# Sheet1.net
KiCad netlist of a schematic drawn in Altium Designer
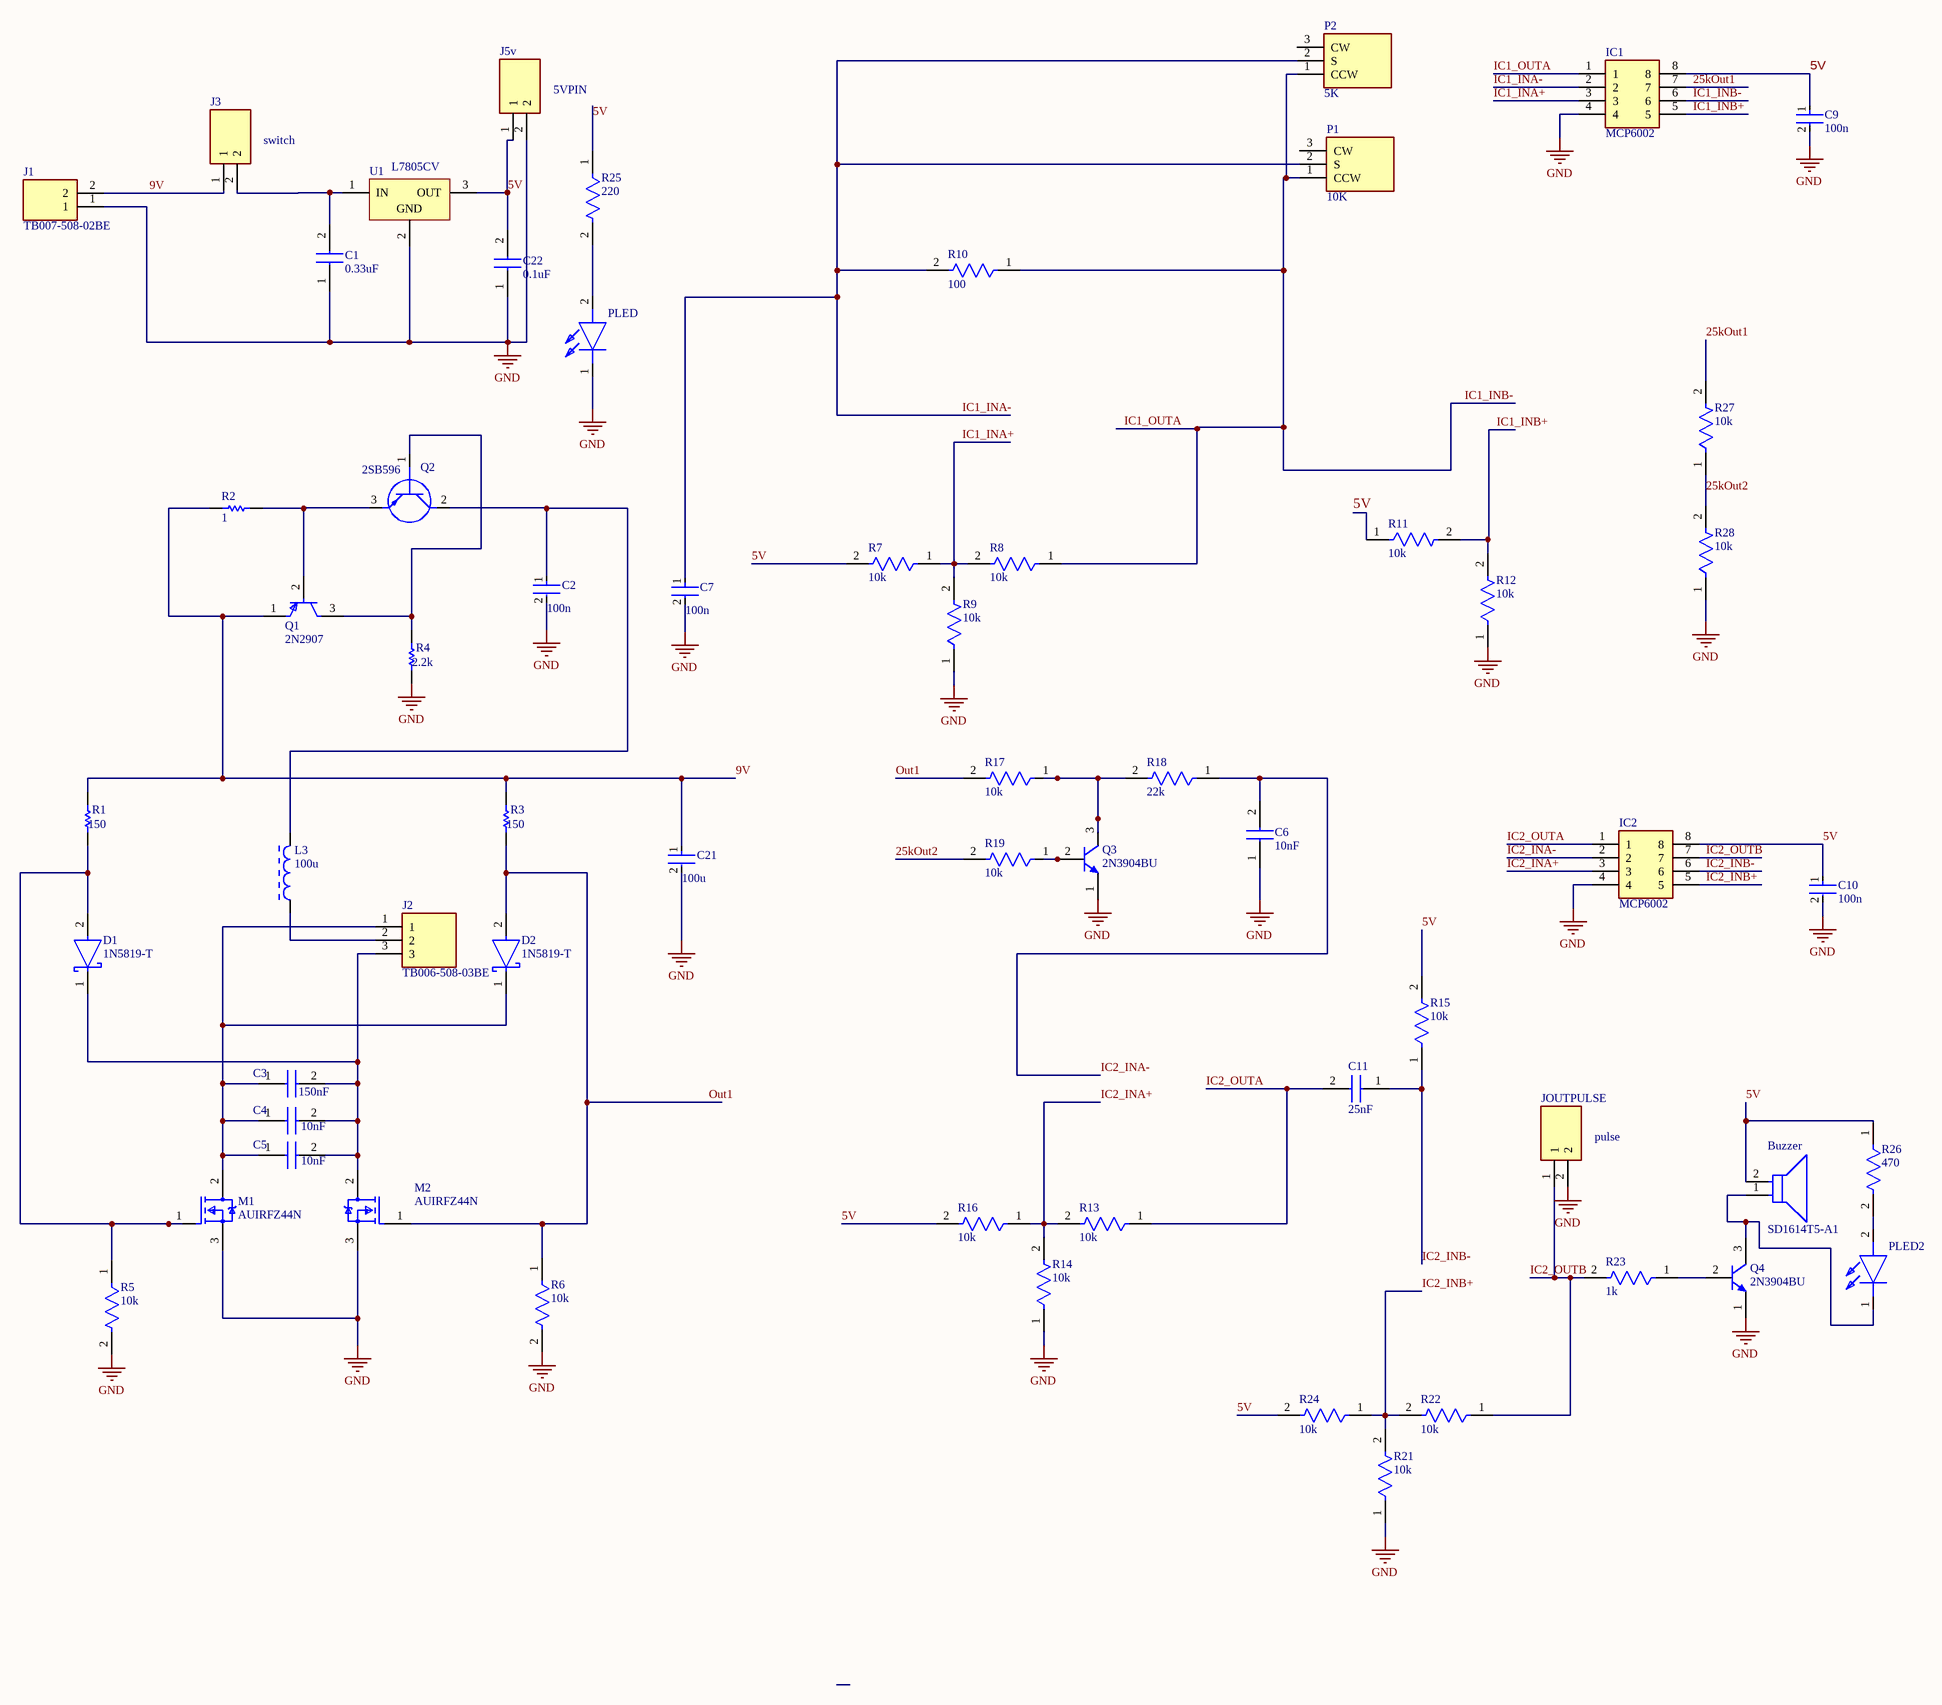
[diagram p0: Sheet1.SchDoc]

(export (version "E")
  (design (tool "Eeschema 10.0.6"))
  (components
    (comp (ref "Buzzer")
      (value "SD1614T5-A1")
      (footprint "FP-SD1614T5-A1-MFG")
      (description "BUZZER MAGNETIC 5V 80DB 2048HZ 1")
      (libsource (lib "Altium Content Vault") (part "e749a21513d54f03b70f810f265f423"))
    )
    (comp (ref "C1")
      (value "0.33uF")
      (footprint "SamacSys:C320C334M5U5TA7301")
      (description "Capacitor")
      (fields
        (field (name "MANUFACTURER_PART_NUMBER") "C320C334M5U5TA7301")
        (field (name "MOUSER PART NUMBER") "80-C320C334M5U5TATU")
      )
      (libsource (lib "*") (part "C320C334M5U5TA7301"))
    )
    (comp (ref "C2")
      (value "100n")
      (footprint "FP-RCE1K1-2_5-MFG")
      (description "Cap Ceramic Monolithic 100nF 100V 10% Thru-Hole Bulk")
      (fields (field (name "TOLERANCE") "10%"))
      (libsource (lib "Altium Content Vault") (part "02cd4be3c70576c341d710602a673aa"))
    )
    (comp (ref "C3")
      (value "150nF")
      (footprint "SamacSys:RDER72J154K5E1H03A")
      (description "Capacitor")
      (fields
        (field (name "MANUFACTURER_PART_NUMBER") "RDER72J154K5E1H03A")
        (field (name "MOUSER PART NUMBER") "81-RDER72J154K5E1H3A")
      )
      (libsource (lib "*") (part "RDER72J154K5E1H03A"))
    )
    (comp (ref "C4")
      (value "10nF")
      (footprint "SamacSys:C315C103K5R5TA")
      (description "Capacitor")
      (fields
        (field (name "MANUFACTURER_PART_NUMBER") "C315C103K5R5TA")
        (field (name "MOUSER PART NUMBER") "80-C315C103K5R")
      )
      (libsource (lib "*") (part "C315C103K5R5TA"))
    )
    (comp (ref "C5")
      (value "10nF")
      (footprint "SamacSys:C315C103K5R5TA")
      (description "Capacitor")
      (fields
        (field (name "MANUFACTURER_PART_NUMBER") "C315C103K5R5TA")
        (field (name "MOUSER PART NUMBER") "80-C315C103K5R")
      )
      (libsource (lib "*") (part "C315C103K5R5TA"))
    )
    (comp (ref "C6")
      (value "10nF")
      (footprint "SamacSys:C315C103K5R5TA")
      (description "Capacitor")
      (fields
        (field (name "MANUFACTURER_PART_NUMBER") "C315C103K5R5TA")
        (field (name "MOUSER PART NUMBER") "80-C315C103K5R")
      )
      (libsource (lib "*") (part "C315C103K5R5TA"))
    )
    (comp (ref "C7")
      (value "100n")
      (footprint "FP-RCE1K1-2_5-MFG")
      (description "Cap Ceramic Monolithic 100nF 100V 10% Thru-Hole Bulk")
      (fields (field (name "TOLERANCE") "10%"))
      (libsource (lib "Altium Content Vault") (part "02cd4be3c70576c341d710602a673aa"))
    )
    (comp (ref "C9")
      (value "100n")
      (footprint "FP-RCE1K1-2_5-MFG")
      (description "Cap Ceramic Monolithic 100nF 100V 10% Thru-Hole Bulk")
      (fields (field (name "TOLERANCE") "10%"))
      (libsource (lib "Altium Content Vault") (part "02cd4be3c70576c341d710602a673aa"))
    )
    (comp (ref "C10")
      (value "100n")
      (footprint "FP-RCE1K1-2_5-MFG")
      (description "Cap Ceramic Monolithic 100nF 100V 10% Thru-Hole Bulk")
      (fields (field (name "TOLERANCE") "10%"))
      (libsource (lib "Altium Content Vault") (part "02cd4be3c70576c341d710602a673aa"))
    )
    (comp (ref "C11")
      (value "25nF")
      (footprint "SamacSys:C315C103K5R5TA")
      (description "Capacitor")
      (fields
        (field (name "MANUFACTURER_PART_NUMBER") "C315C103K5R5TA")
        (field (name "MOUSER PART NUMBER") "80-C315C103K5R")
      )
      (libsource (lib "*") (part "C315C103K5R5TA"))
    )
    (comp (ref "C21")
      (value "100u")
      (footprint "FP-RCE1K1-2_5-MFG")
      (description "Cap Ceramic Monolithic 100nF 100V 10% Thru-Hole Bulk")
      (fields (field (name "TOLERANCE") "10%"))
      (libsource (lib "Altium Content Vault") (part "02cd4be3c70576c341d710602a673aa"))
    )
    (comp (ref "C22")
      (value "0.1uF")
      (footprint "SamacSys:FK20")
      (description "Capacitor")
      (fields (field (name "MANUFACTURER_PART_NUMBER") "FK20C0G1H104JN000"))
      (libsource (lib "*") (part "FK20C0G1H104JN000"))
    )
    (comp (ref "D1")
      (value "1N5819-T")
      (footprint "FP-DO-41_Plastic-MFG")
      (description "DIODE SCHOTTKY 40V 1A DO41")
      (fields
        (field (name "MANUFACTURER") "Diodes Inc.")
        (field (name "OCTOPART") "https://octopart.com/1n5819-t-diodes+inc.-55389586")
      )
      (libsource (lib "Altium Content Vault") (part "1d6ec82d83fb6aee721767c19dac4b9"))
    )
    (comp (ref "D2")
      (value "1N5819-T")
      (footprint "FP-DO-41_Plastic-MFG")
      (description "DIODE SCHOTTKY 40V 1A DO41")
      (fields
        (field (name "MANUFACTURER") "Diodes Inc.")
        (field (name "OCTOPART") "https://octopart.com/1n5819-t-diodes+inc.-55389586")
      )
      (libsource (lib "Altium Content Vault") (part "1d6ec82d83fb6aee721767c19dac4b9"))
    )
    (comp (ref "IC1")
      (value "MCP6002")
      (footprint "SamacSys:DIPS762W61P254L1016H525Q8N")
      (description "Connector")
      (fields (field (name "MANUFACTURER_PART_NUMBER") "A 08-LC-TT"))
      (libsource (lib "*") (part "A_08-LC-TT"))
    )
    (comp (ref "IC2")
      (value "MCP6002")
      (footprint "SamacSys:DIPS762W61P254L1016H525Q8N")
      (description "Connector")
      (fields (field (name "MANUFACTURER_PART_NUMBER") "A 08-LC-TT"))
      (libsource (lib "*") (part "A_08-LC-TT"))
    )
    (comp (ref "J1")
      (value "TB007-508-02BE")
      (footprint "SamacSys:TB00750802BE")
      (description "Connector")
      (fields (field (name "MOUSER PART NUMBER") "490-TB007-508-02BE"))
      (libsource (lib "*") (part "TB007-508-02BE"))
    )
    (comp (ref "J2")
      (value "TB006-508-03BE")
      (footprint "SamacSys:TB00650803BE")
      (description "Connector")
      (fields (field (name "MOUSER PART NUMBER") "490-TB006-508-03BE"))
      (libsource (lib "*") (part "TB006-508-03BE"))
    )
    (comp (ref "J3")
      (value "switch")
      (footprint "SamacSys:HDRV2W64P0X254_1X2_508X254X864P")
      (description "Connector")
      (fields
        (field (name "MANUFACTURER_PART_NUMBER") "M20-9990245")
        (field (name "MOUSER PART NUMBER") "855-M20-9990245")
      )
      (libsource (lib "*") (part "M20-9990245"))
    )
    (comp (ref "J5v")
      (value "5VPIN")
      (footprint "SamacSys:HDRV2W64P0X254_1X2_508X254X864P")
      (description "Connector")
      (fields
        (field (name "MANUFACTURER_PART_NUMBER") "M20-9990245")
        (field (name "MOUSER PART NUMBER") "855-M20-9990245")
      )
      (libsource (lib "*") (part "M20-9990245"))
    )
    (comp (ref "JOUTPULSE")
      (value "pulse")
      (footprint "SamacSys:HDRV2W64P0X254_1X2_508X254X864P")
      (description "Connector")
      (fields
        (field (name "MANUFACTURER_PART_NUMBER") "M20-9990245")
        (field (name "MOUSER PART NUMBER") "855-M20-9990245")
      )
      (libsource (lib "*") (part "M20-9990245"))
    )
    (comp (ref "L3")
      (value "100u")
      (footprint "BOUR-77F-2_V1")
      (fields (field (name "PARTNUMBER") "77F471J-TR-RC") (field (name "MANUFACTURER") "Bourns"))
      (libsource (lib "Altium Content Vault") (part "BOUR-IND-2A"))
    )
    (comp (ref "M1")
      (value "AUIRFZ44N")
      (footprint "FP-TO-220AB-MFG")
      (libsource (lib "Altium Content Vault") (part "535c4fe1372f32a24686ada0a8c11ba"))
    )
    (comp (ref "M2")
      (value "AUIRFZ44N")
      (footprint "FP-TO-220AB-MFG")
      (libsource (lib "Altium Content Vault") (part "535c4fe1372f32a24686ada0a8c11ba"))
    )
    (comp (ref "P1")
      (value "10K")
      (footprint "SamacSys:P160KN0QC15B10K")
      (description "Variable Resistor")
      (fields
        (field (name "MANUFACTURER_PART_NUMBER") "P160KN-0QC15B10K")
        (field (name "MOUSER PART NUMBER") "858-P160KN-0QC15B10K")
      )
      (libsource (lib "*") (part "P160KN-0QC15B10K"))
    )
    (comp (ref "P2")
      (value "5K")
      (footprint "SamacSys:P160KN0QC15B10K")
      (description "Variable Resistor")
      (fields
        (field (name "MANUFACTURER_PART_NUMBER") "P160KN-0QC15B10K")
        (field (name "MOUSER PART NUMBER") "858-P160KN-0QC15B10K")
      )
      (libsource (lib "*") (part "P160KN-0QC15B10K"))
    )
    (comp (ref "PLED")
      (value "151051RS11000")
      (footprint "SamacSys:151051RS11000")
      (description "LED")
      (fields (field (name "MOUSER PART NUMBER") "710-151051RS11000"))
      (libsource (lib "*") (part "151051RS11000"))
    )
    (comp (ref "PLED2")
      (value "151051RS11000")
      (footprint "SamacSys:151051RS11000")
      (description "LED")
      (fields (field (name "MOUSER PART NUMBER") "710-151051RS11000"))
      (libsource (lib "*") (part "151051RS11000"))
    )
    (comp (ref "Q1")
      (value "2N2907")
      (footprint "FP-TO-18-MFG")
      (description "2N2907 Small-Signal Bjt To-18 Rohs Compliant: Yes")
      (libsource (lib "Altium Content Vault") (part "15b317111ce8998a8cd3923a58ba97d"))
    )
    (comp (ref "Q2")
      (value "2SB596")
      (footprint "SamacSys:TO254P470X1016X2019-3P")
      (description "Transistor BJT PNP")
      (fields
        (field (name "MANUFACTURER_PART_NUMBER") "TIP42C")
        (field (name "MOUSER PART NUMBER") "512-TIP42C")
      )
      (libsource (lib "*") (part "TIP42C"))
    )
    (comp (ref "Q3")
      (value "2N3904BU")
      (footprint "FAIR-TO-92")
      (description "NPN General-Purpose Amplifier, 40 V VCEO, 0.2 A, -55 to 150 degC, 2-Pin TO-92, RoHS, Bulk")
      (fields (field (name "MANUFACTURER") "FairchildSemiconductor"))
      (libsource (lib "Altium Content Vault") (part "NPN-E1B2C3-3"))
    )
    (comp (ref "Q4")
      (value "2N3904BU")
      (footprint "FAIR-TO-92")
      (description "NPN General-Purpose Amplifier, 40 V VCEO, 0.2 A, -55 to 150 degC, 2-Pin TO-92, RoHS, Bulk")
      (fields (field (name "MANUFACTURER") "FairchildSemiconductor"))
      (libsource (lib "Altium Content Vault") (part "NPN-E1B2C3-3"))
    )
    (comp (ref "R1")
      (value "150")
      (footprint "RESA60-630X240")
      (description "Axial Resistor, 1 KOhm, +/- 1%, 250 mW, -55 to 155 degC, 2-Pin THD, RoHS, Bulk")
      (fields (field (name "TOLERANCE") "1%"))
      (libsource (lib "Altium Content Vault") (part "RES-2"))
    )
    (comp (ref "R2")
      (value "1")
      (footprint "RESA60-630X240")
      (description "Axial Resistor, 1 KOhm, +/- 1%, 250 mW, -55 to 155 degC, 2-Pin THD, RoHS, Bulk")
      (fields (field (name "TOLERANCE") "1%"))
      (libsource (lib "Altium Content Vault") (part "RES-2"))
    )
    (comp (ref "R3")
      (value "150")
      (footprint "RESA60-630X240")
      (description "Axial Resistor, 1 KOhm, +/- 1%, 250 mW, -55 to 155 degC, 2-Pin THD, RoHS, Bulk")
      (fields (field (name "TOLERANCE") "1%"))
      (libsource (lib "Altium Content Vault") (part "RES-2"))
    )
    (comp (ref "R4")
      (value "2.2k")
      (footprint "RESA60-630X240")
      (description "Axial Resistor, 1 KOhm, +/- 1%, 250 mW, -55 to 155 degC, 2-Pin THD, RoHS, Bulk")
      (fields (field (name "TOLERANCE") "1%"))
      (libsource (lib "Altium Content Vault") (part "RES-2"))
    )
    (comp (ref "R5")
      (value "10k")
      (footprint "FP-CF18-MFG")
      (description "RES 10K OHM 1/8W 5% CF AXIAL")
      (fields
        (field (name "MANUFACTURER PART NUMBER") "CF18JT10K0")
        (field (name "MANUFACTURER") "Stackpole Electronics")
      )
      (libsource (lib "Altium Content Vault") (part "1029c3af85768c4190bb7ad29bc67b5"))
    )
    (comp (ref "R6")
      (value "10k")
      (footprint "FP-CF18-MFG")
      (description "RES 10K OHM 1/8W 5% CF AXIAL")
      (fields
        (field (name "MANUFACTURER PART NUMBER") "CF18JT10K0")
        (field (name "MANUFACTURER") "Stackpole Electronics")
      )
      (libsource (lib "Altium Content Vault") (part "1029c3af85768c4190bb7ad29bc67b5"))
    )
    (comp (ref "R7")
      (value "10k")
      (footprint "FP-CF18-MFG")
      (description "RES 10K OHM 1/8W 5% CF AXIAL")
      (fields
        (field (name "MANUFACTURER PART NUMBER") "CF18JT10K0")
        (field (name "MANUFACTURER") "Stackpole Electronics")
      )
      (libsource (lib "Altium Content Vault") (part "1029c3af85768c4190bb7ad29bc67b5"))
    )
    (comp (ref "R8")
      (value "10k")
      (footprint "FP-CF18-MFG")
      (description "RES 10K OHM 1/8W 5% CF AXIAL")
      (fields
        (field (name "MANUFACTURER PART NUMBER") "CF18JT10K0")
        (field (name "MANUFACTURER") "Stackpole Electronics")
      )
      (libsource (lib "Altium Content Vault") (part "1029c3af85768c4190bb7ad29bc67b5"))
    )
    (comp (ref "R9")
      (value "10k")
      (footprint "FP-CF18-MFG")
      (description "RES 10K OHM 1/8W 5% CF AXIAL")
      (fields
        (field (name "MANUFACTURER PART NUMBER") "CF18JT10K0")
        (field (name "MANUFACTURER") "Stackpole Electronics")
      )
      (libsource (lib "Altium Content Vault") (part "1029c3af85768c4190bb7ad29bc67b5"))
    )
    (comp (ref "R10")
      (value "100")
      (footprint "FP-CF18-MFG")
      (description "RES 10K OHM 1/8W 5% CF AXIAL")
      (fields
        (field (name "MANUFACTURER PART NUMBER") "CF18JT10K0")
        (field (name "MANUFACTURER") "Stackpole Electronics")
      )
      (libsource (lib "Altium Content Vault") (part "1029c3af85768c4190bb7ad29bc67b5"))
    )
    (comp (ref "R11")
      (value "10k")
      (footprint "FP-CF18-MFG")
      (description "RES 10K OHM 1/8W 5% CF AXIAL")
      (fields
        (field (name "MANUFACTURER PART NUMBER") "CF18JT10K0")
        (field (name "MANUFACTURER") "Stackpole Electronics")
      )
      (libsource (lib "Altium Content Vault") (part "1029c3af85768c4190bb7ad29bc67b5"))
    )
    (comp (ref "R12")
      (value "10k")
      (footprint "FP-CF18-MFG")
      (description "RES 10K OHM 1/8W 5% CF AXIAL")
      (fields
        (field (name "MANUFACTURER PART NUMBER") "CF18JT10K0")
        (field (name "MANUFACTURER") "Stackpole Electronics")
      )
      (libsource (lib "Altium Content Vault") (part "1029c3af85768c4190bb7ad29bc67b5"))
    )
    (comp (ref "R13")
      (value "10k")
      (footprint "FP-CF18-MFG")
      (description "RES 10K OHM 1/8W 5% CF AXIAL")
      (fields
        (field (name "MANUFACTURER PART NUMBER") "CF18JT10K0")
        (field (name "MANUFACTURER") "Stackpole Electronics")
      )
      (libsource (lib "Altium Content Vault") (part "1029c3af85768c4190bb7ad29bc67b5"))
    )
    (comp (ref "R14")
      (value "10k")
      (footprint "FP-CF18-MFG")
      (description "RES 10K OHM 1/8W 5% CF AXIAL")
      (fields
        (field (name "MANUFACTURER PART NUMBER") "CF18JT10K0")
        (field (name "MANUFACTURER") "Stackpole Electronics")
      )
      (libsource (lib "Altium Content Vault") (part "1029c3af85768c4190bb7ad29bc67b5"))
    )
    (comp (ref "R15")
      (value "10k")
      (footprint "FP-CF18-MFG")
      (description "RES 10K OHM 1/8W 5% CF AXIAL")
      (fields
        (field (name "MANUFACTURER PART NUMBER") "CF18JT10K0")
        (field (name "MANUFACTURER") "Stackpole Electronics")
      )
      (libsource (lib "Altium Content Vault") (part "1029c3af85768c4190bb7ad29bc67b5"))
    )
    (comp (ref "R16")
      (value "10k")
      (footprint "FP-CF18-MFG")
      (description "RES 10K OHM 1/8W 5% CF AXIAL")
      (fields
        (field (name "MANUFACTURER PART NUMBER") "CF18JT10K0")
        (field (name "MANUFACTURER") "Stackpole Electronics")
      )
      (libsource (lib "Altium Content Vault") (part "1029c3af85768c4190bb7ad29bc67b5"))
    )
    (comp (ref "R17")
      (value "10k")
      (footprint "FP-CF18-MFG")
      (description "RES 10K OHM 1/8W 5% CF AXIAL")
      (fields
        (field (name "MANUFACTURER PART NUMBER") "CF18JT10K0")
        (field (name "MANUFACTURER") "Stackpole Electronics")
      )
      (libsource (lib "Altium Content Vault") (part "1029c3af85768c4190bb7ad29bc67b5"))
    )
    (comp (ref "R18")
      (value "22k")
      (footprint "FP-CF18-MFG")
      (description "RES 10K OHM 1/8W 5% CF AXIAL")
      (fields
        (field (name "MANUFACTURER PART NUMBER") "CF18JT10K0")
        (field (name "MANUFACTURER") "Stackpole Electronics")
      )
      (libsource (lib "Altium Content Vault") (part "1029c3af85768c4190bb7ad29bc67b5"))
    )
    (comp (ref "R19")
      (value "10k")
      (footprint "FP-CF18-MFG")
      (description "RES 10K OHM 1/8W 5% CF AXIAL")
      (fields
        (field (name "MANUFACTURER PART NUMBER") "CF18JT10K0")
        (field (name "MANUFACTURER") "Stackpole Electronics")
      )
      (libsource (lib "Altium Content Vault") (part "1029c3af85768c4190bb7ad29bc67b5"))
    )
    (comp (ref "R21")
      (value "10k")
      (footprint "FP-CF18-MFG")
      (description "RES 10K OHM 1/8W 5% CF AXIAL")
      (fields
        (field (name "MANUFACTURER PART NUMBER") "CF18JT10K0")
        (field (name "MANUFACTURER") "Stackpole Electronics")
      )
      (libsource (lib "Altium Content Vault") (part "1029c3af85768c4190bb7ad29bc67b5"))
    )
    (comp (ref "R22")
      (value "10k")
      (footprint "FP-CF18-MFG")
      (description "RES 10K OHM 1/8W 5% CF AXIAL")
      (fields
        (field (name "MANUFACTURER PART NUMBER") "CF18JT10K0")
        (field (name "MANUFACTURER") "Stackpole Electronics")
      )
      (libsource (lib "Altium Content Vault") (part "1029c3af85768c4190bb7ad29bc67b5"))
    )
    (comp (ref "R23")
      (value "1k")
      (footprint "FP-CF18-MFG")
      (description "RES 10K OHM 1/8W 5% CF AXIAL")
      (fields
        (field (name "MANUFACTURER PART NUMBER") "CF18JT10K0")
        (field (name "MANUFACTURER") "Stackpole Electronics")
      )
      (libsource (lib "Altium Content Vault") (part "1029c3af85768c4190bb7ad29bc67b5"))
    )
    (comp (ref "R24")
      (value "10k")
      (footprint "FP-CF18-MFG")
      (description "RES 10K OHM 1/8W 5% CF AXIAL")
      (fields
        (field (name "MANUFACTURER PART NUMBER") "CF18JT10K0")
        (field (name "MANUFACTURER") "Stackpole Electronics")
      )
      (libsource (lib "Altium Content Vault") (part "1029c3af85768c4190bb7ad29bc67b5"))
    )
    (comp (ref "R25")
      (value "220")
      (footprint "FP-CF18-MFG")
      (description "RES 10K OHM 1/8W 5% CF AXIAL")
      (fields
        (field (name "MANUFACTURER PART NUMBER") "CF18JT10K0")
        (field (name "MANUFACTURER") "Stackpole Electronics")
      )
      (libsource (lib "Altium Content Vault") (part "1029c3af85768c4190bb7ad29bc67b5"))
    )
    (comp (ref "R26")
      (value "470")
      (footprint "FP-CF18-MFG")
      (description "RES 10K OHM 1/8W 5% CF AXIAL")
      (fields
        (field (name "MANUFACTURER PART NUMBER") "CF18JT10K0")
        (field (name "MANUFACTURER") "Stackpole Electronics")
      )
      (libsource (lib "Altium Content Vault") (part "1029c3af85768c4190bb7ad29bc67b5"))
    )
    (comp (ref "R27")
      (value "10k")
      (footprint "FP-CF18-MFG")
      (description "RES 10K OHM 1/8W 5% CF AXIAL")
      (fields
        (field (name "MANUFACTURER PART NUMBER") "CF18JT10K0")
        (field (name "MANUFACTURER") "Stackpole Electronics")
      )
      (libsource (lib "Altium Content Vault") (part "1029c3af85768c4190bb7ad29bc67b5"))
    )
    (comp (ref "R28")
      (value "10k")
      (footprint "FP-CF18-MFG")
      (description "RES 10K OHM 1/8W 5% CF AXIAL")
      (fields
        (field (name "MANUFACTURER PART NUMBER") "CF18JT10K0")
        (field (name "MANUFACTURER") "Stackpole Electronics")
      )
      (libsource (lib "Altium Content Vault") (part "1029c3af85768c4190bb7ad29bc67b5"))
    )
    (comp (ref "U1")
      (value "L7805CV")
      (footprint "TO220")
      (description "Positive Voltage Regulator, 5V, 3-Pin TO-220")
      (libsource (lib "Altium Content Vault") (part "PM-REG-L4940-SIL3"))
    )
  )
  (nets
    (net (code "1") (name "/5V") (class "Default")
      (node (ref "Buzzer") (pin "2") (pinfunction "A_2") (pintype "passive"))
      (node (ref "C10") (pin "1") (pinfunction "1_1") (pintype "passive"))
      (node (ref "C22") (pin "2") (pinfunction "2_2") (pintype "passive"))
      (node (ref "C9") (pin "1") (pinfunction "1_1") (pintype "passive"))
      (node (ref "IC1") (pin "8") (pinfunction "8_8") (pintype "passive"))
      (node (ref "IC2") (pin "8") (pinfunction "8_8") (pintype "passive"))
      (node (ref "J5v") (pin "1") (pinfunction "1_1") (pintype "passive"))
      (node (ref "R11") (pin "1") (pinfunction "1_1") (pintype "passive"))
      (node (ref "R15") (pin "2") (pinfunction "2_2") (pintype "passive"))
      (node (ref "R16") (pin "2") (pinfunction "2_2") (pintype "passive"))
      (node (ref "R24") (pin "2") (pinfunction "2_2") (pintype "passive"))
      (node (ref "R25") (pin "1") (pinfunction "1_1") (pintype "passive"))
      (node (ref "R26") (pin "1") (pinfunction "1_1") (pintype "passive"))
      (node (ref "R7") (pin "2") (pinfunction "2_2") (pintype "passive"))
      (node (ref "U1") (pin "3") (pinfunction "OUT_3") (pintype "power_in"))
    )
    (net (code "2") (name "/9V") (class "Default")
      (node (ref "C21") (pin "1") (pinfunction "1_1") (pintype "passive"))
      (node (ref "J1") (pin "2") (pinfunction "2_2") (pintype "passive"))
      (node (ref "J3") (pin "1") (pinfunction "1_1") (pintype "passive"))
      (node (ref "Q1") (pin "1") (pinfunction "E_1") (pintype "passive"))
      (node (ref "R1") (pin "2") (pinfunction "2_2") (pintype "passive"))
      (node (ref "R2") (pin "1") (pinfunction "1_1") (pintype "passive"))
      (node (ref "R3") (pin "2") (pinfunction "2_2") (pintype "passive"))
    )
    (net (code "3") (name "/25kOut1") (class "Default")
      (node (ref "IC1") (pin "7") (pinfunction "7_7") (pintype "passive"))
      (node (ref "R27") (pin "2") (pinfunction "2_2") (pintype "passive"))
    )
    (net (code "4") (name "/25kOut2") (class "Default")
      (node (ref "R19") (pin "2") (pinfunction "2_2") (pintype "passive"))
      (node (ref "R27") (pin "1") (pinfunction "1_1") (pintype "passive"))
      (node (ref "R28") (pin "2") (pinfunction "2_2") (pintype "passive"))
    )
    (net (code "5") (name "/IC1_INA+") (class "Default")
      (node (ref "IC1") (pin "3") (pinfunction "3_3") (pintype "passive"))
      (node (ref "R7") (pin "1") (pinfunction "1_1") (pintype "passive"))
      (node (ref "R8") (pin "2") (pinfunction "2_2") (pintype "passive"))
      (node (ref "R9") (pin "2") (pinfunction "2_2") (pintype "passive"))
    )
    (net (code "6") (name "/IC1_INA-") (class "Default")
      (node (ref "C7") (pin "1") (pinfunction "1_1") (pintype "passive"))
      (node (ref "IC1") (pin "2") (pinfunction "2_2") (pintype "passive"))
      (node (ref "P1") (pin "2") (pinfunction "S_2") (pintype "passive"))
      (node (ref "P2") (pin "2") (pinfunction "S_2") (pintype "passive"))
      (node (ref "R10") (pin "2") (pinfunction "2_2") (pintype "passive"))
    )
    (net (code "7") (name "/IC1_INB+") (class "Default")
      (node (ref "IC1") (pin "5") (pinfunction "5_5") (pintype "passive"))
      (node (ref "R11") (pin "2") (pinfunction "2_2") (pintype "passive"))
      (node (ref "R12") (pin "2") (pinfunction "2_2") (pintype "passive"))
    )
    (net (code "8") (name "/IC1_INB-") (class "Default")
      (node (ref "IC1") (pin "1") (pinfunction "1_1") (pintype "passive"))
      (node (ref "IC1") (pin "6") (pinfunction "6_6") (pintype "passive"))
      (node (ref "P1") (pin "1") (pinfunction "CCW_1") (pintype "passive"))
      (node (ref "P2") (pin "1") (pinfunction "CCW_1") (pintype "passive"))
      (node (ref "R10") (pin "1") (pinfunction "1_1") (pintype "passive"))
      (node (ref "R8") (pin "1") (pinfunction "1_1") (pintype "passive"))
    )
    (net (code "9") (name "/IC2_INA+") (class "Default")
      (node (ref "IC2") (pin "3") (pinfunction "3_3") (pintype "passive"))
      (node (ref "R13") (pin "2") (pinfunction "2_2") (pintype "passive"))
      (node (ref "R14") (pin "2") (pinfunction "2_2") (pintype "passive"))
      (node (ref "R16") (pin "1") (pinfunction "1_1") (pintype "passive"))
    )
    (net (code "10") (name "/IC2_INA-") (class "Default")
      (node (ref "C6") (pin "2") (pinfunction "2_2") (pintype "passive"))
      (node (ref "IC2") (pin "2") (pinfunction "2_2") (pintype "passive"))
      (node (ref "R18") (pin "1") (pinfunction "1_1") (pintype "passive"))
    )
    (net (code "11") (name "/IC2_INB+") (class "Default")
      (node (ref "IC2") (pin "5") (pinfunction "5_5") (pintype "passive"))
      (node (ref "R21") (pin "2") (pinfunction "2_2") (pintype "passive"))
      (node (ref "R22") (pin "2") (pinfunction "2_2") (pintype "passive"))
      (node (ref "R24") (pin "1") (pinfunction "1_1") (pintype "passive"))
    )
    (net (code "12") (name "/IC2_INB-") (class "Default")
      (node (ref "C11") (pin "1") (pinfunction "1_1") (pintype "passive"))
      (node (ref "IC2") (pin "6") (pinfunction "6_6") (pintype "passive"))
      (node (ref "R15") (pin "1") (pinfunction "1_1") (pintype "passive"))
    )
    (net (code "13") (name "/IC2_OUTA") (class "Default")
      (node (ref "C11") (pin "2") (pinfunction "2_2") (pintype "passive"))
      (node (ref "IC2") (pin "1") (pinfunction "1_1") (pintype "passive"))
      (node (ref "R13") (pin "1") (pinfunction "1_1") (pintype "passive"))
    )
    (net (code "14") (name "/IC2_OUTB") (class "Default")
      (node (ref "IC2") (pin "7") (pinfunction "7_7") (pintype "passive"))
      (node (ref "JOUTPULSE") (pin "1") (pinfunction "1_1") (pintype "passive"))
      (node (ref "R22") (pin "1") (pinfunction "1_1") (pintype "passive"))
      (node (ref "R23") (pin "2") (pinfunction "2_2") (pintype "passive"))
    )
    (net (code "15") (name "/Out1") (class "Default")
      (node (ref "D2") (pin "2") (pinfunction "A_2") (pintype "passive"))
      (node (ref "M2") (pin "1") (pinfunction "G_1") (pintype "passive"))
      (node (ref "R17") (pin "2") (pinfunction "2_2") (pintype "passive"))
      (node (ref "R3") (pin "1") (pinfunction "1_1") (pintype "passive"))
      (node (ref "R6") (pin "1") (pinfunction "1_1") (pintype "passive"))
    )
    (net (code "16") (name "GND") (class "Default")
      (node (ref "C1") (pin "1") (pinfunction "1_1") (pintype "passive"))
      (node (ref "C10") (pin "2") (pinfunction "2_2") (pintype "passive"))
      (node (ref "C2") (pin "2") (pinfunction "2_2") (pintype "passive"))
      (node (ref "C21") (pin "2") (pinfunction "2_2") (pintype "passive"))
      (node (ref "C22") (pin "1") (pinfunction "1_1") (pintype "passive"))
      (node (ref "C6") (pin "1") (pinfunction "1_1") (pintype "passive"))
      (node (ref "C7") (pin "2") (pinfunction "2_2") (pintype "passive"))
      (node (ref "C9") (pin "2") (pinfunction "2_2") (pintype "passive"))
      (node (ref "IC1") (pin "4") (pinfunction "4_4") (pintype "passive"))
      (node (ref "IC2") (pin "4") (pinfunction "4_4") (pintype "passive"))
      (node (ref "J1") (pin "1") (pinfunction "1_1") (pintype "passive"))
      (node (ref "J5v") (pin "2") (pinfunction "2_2") (pintype "passive"))
      (node (ref "JOUTPULSE") (pin "2") (pinfunction "2_2") (pintype "passive"))
      (node (ref "M1") (pin "3") (pinfunction "S_3") (pintype "passive"))
      (node (ref "M2") (pin "3") (pinfunction "S_3") (pintype "passive"))
      (node (ref "PLED") (pin "1") (pinfunction "K_1") (pintype "passive"))
      (node (ref "Q3") (pin "1") (pinfunction "E_1") (pintype "passive"))
      (node (ref "Q4") (pin "1") (pinfunction "E_1") (pintype "passive"))
      (node (ref "R12") (pin "1") (pinfunction "1_1") (pintype "passive"))
      (node (ref "R14") (pin "1") (pinfunction "1_1") (pintype "passive"))
      (node (ref "R21") (pin "1") (pinfunction "1_1") (pintype "passive"))
      (node (ref "R28") (pin "1") (pinfunction "1_1") (pintype "passive"))
      (node (ref "R4") (pin "1") (pinfunction "1_1") (pintype "passive"))
      (node (ref "R5") (pin "2") (pinfunction "2_2") (pintype "passive"))
      (node (ref "R6") (pin "2") (pinfunction "2_2") (pintype "passive"))
      (node (ref "R9") (pin "1") (pinfunction "1_1") (pintype "passive"))
      (node (ref "U1") (pin "2") (pinfunction "GND_2") (pintype "power_in"))
    )
    (net (code "17") (name "Net-(Buzzer-C)") (class "Default")
      (node (ref "Buzzer") (pin "1") (pinfunction "C_1") (pintype "passive"))
      (node (ref "PLED2") (pin "1") (pinfunction "K_1") (pintype "passive"))
      (node (ref "Q4") (pin "3") (pinfunction "C_3") (pintype "passive"))
    )
    (net (code "18") (name "Net-(D1-A)") (class "Default")
      (node (ref "D1") (pin "2") (pinfunction "A_2") (pintype "passive"))
      (node (ref "M1") (pin "1") (pinfunction "G_1") (pintype "passive"))
      (node (ref "R1") (pin "1") (pinfunction "1_1") (pintype "passive"))
      (node (ref "R5") (pin "1") (pinfunction "1_1") (pintype "passive"))
    )
    (net (code "19") (name "Net-(D1-C)") (class "Default")
      (node (ref "C3") (pin "2") (pinfunction "2_2") (pintype "passive"))
      (node (ref "C4") (pin "2") (pinfunction "2_2") (pintype "passive"))
      (node (ref "C5") (pin "2") (pinfunction "2_2") (pintype "passive"))
      (node (ref "D1") (pin "1") (pinfunction "C_1") (pintype "passive"))
      (node (ref "J2") (pin "3") (pinfunction "3_3") (pintype "passive"))
      (node (ref "M2") (pin "2") (pinfunction "D_2") (pintype "passive"))
    )
    (net (code "20") (name "Net-(D2-C)") (class "Default")
      (node (ref "C3") (pin "1") (pinfunction "1_1") (pintype "passive"))
      (node (ref "C4") (pin "1") (pinfunction "1_1") (pintype "passive"))
      (node (ref "C5") (pin "1") (pinfunction "1_1") (pintype "passive"))
      (node (ref "D2") (pin "1") (pinfunction "C_1") (pintype "passive"))
      (node (ref "J2") (pin "1") (pinfunction "1_1") (pintype "passive"))
      (node (ref "M1") (pin "2") (pinfunction "D_2") (pintype "passive"))
    )
    (net (code "21") (name "Net-(J2-Pad2)") (class "Default")
      (node (ref "J2") (pin "2") (pinfunction "2_2") (pintype "passive"))
      (node (ref "L3") (pin "1") (pinfunction "1_1") (pintype "passive"))
    )
    (net (code "22") (name "Net-(PLED-A)") (class "Default")
      (node (ref "PLED") (pin "2") (pinfunction "A_2") (pintype "passive"))
      (node (ref "R25") (pin "2") (pinfunction "2_2") (pintype "passive"))
    )
    (net (code "23") (name "Net-(PLED2-A)") (class "Default")
      (node (ref "PLED2") (pin "2") (pinfunction "A_2") (pintype "passive"))
      (node (ref "R26") (pin "2") (pinfunction "2_2") (pintype "passive"))
    )
    (net (code "24") (name "Net-(Q1-B)") (class "Default")
      (node (ref "Q1") (pin "2") (pinfunction "B_2") (pintype "passive"))
      (node (ref "Q2") (pin "3") (pinfunction "E_3") (pintype "passive"))
      (node (ref "R2") (pin "2") (pinfunction "2_2") (pintype "passive"))
    )
    (net (code "25") (name "Net-(Q1-C)") (class "Default")
      (node (ref "Q1") (pin "3") (pinfunction "C_3") (pintype "passive"))
      (node (ref "Q2") (pin "1") (pinfunction "B_1") (pintype "passive"))
      (node (ref "R4") (pin "2") (pinfunction "2_2") (pintype "passive"))
    )
    (net (code "26") (name "Net-(Q2-C)") (class "Default")
      (node (ref "C2") (pin "1") (pinfunction "1_1") (pintype "passive"))
      (node (ref "L3") (pin "2") (pinfunction "2_2") (pintype "passive"))
      (node (ref "Q2") (pin "2") (pinfunction "C_2") (pintype "passive"))
    )
    (net (code "27") (name "Net-(Q3-B)") (class "Default")
      (node (ref "Q3") (pin "2") (pinfunction "B_2") (pintype "passive"))
      (node (ref "R19") (pin "1") (pinfunction "1_1") (pintype "passive"))
    )
    (net (code "28") (name "Net-(Q3-C)") (class "Default")
      (node (ref "Q3") (pin "3") (pinfunction "C_3") (pintype "passive"))
      (node (ref "R17") (pin "1") (pinfunction "1_1") (pintype "passive"))
      (node (ref "R18") (pin "2") (pinfunction "2_2") (pintype "passive"))
    )
    (net (code "29") (name "Net-(Q4-B)") (class "Default")
      (node (ref "Q4") (pin "2") (pinfunction "B_2") (pintype "passive"))
      (node (ref "R23") (pin "1") (pinfunction "1_1") (pintype "passive"))
    )
    (net (code "30") (name "Net-(U1-IN)") (class "Default")
      (node (ref "C1") (pin "2") (pinfunction "2_2") (pintype "passive"))
      (node (ref "J3") (pin "2") (pinfunction "2_2") (pintype "passive"))
      (node (ref "U1") (pin "1") (pinfunction "IN_1") (pintype "power_in"))
    )
    (net (code "31") (name "unconnected-(P1-CW-Pad3)") (class "Default")
      (node (ref "P1") (pin "3") (pinfunction "CW_3") (pintype "passive"))
    )
    (net (code "32") (name "unconnected-(P2-CW-Pad3)") (class "Default")
      (node (ref "P2") (pin "3") (pinfunction "CW_3") (pintype "passive"))
    )
  )
)
